# ESP32VGAv2.net
KiCad netlist of a schematic drawn in EAGLE
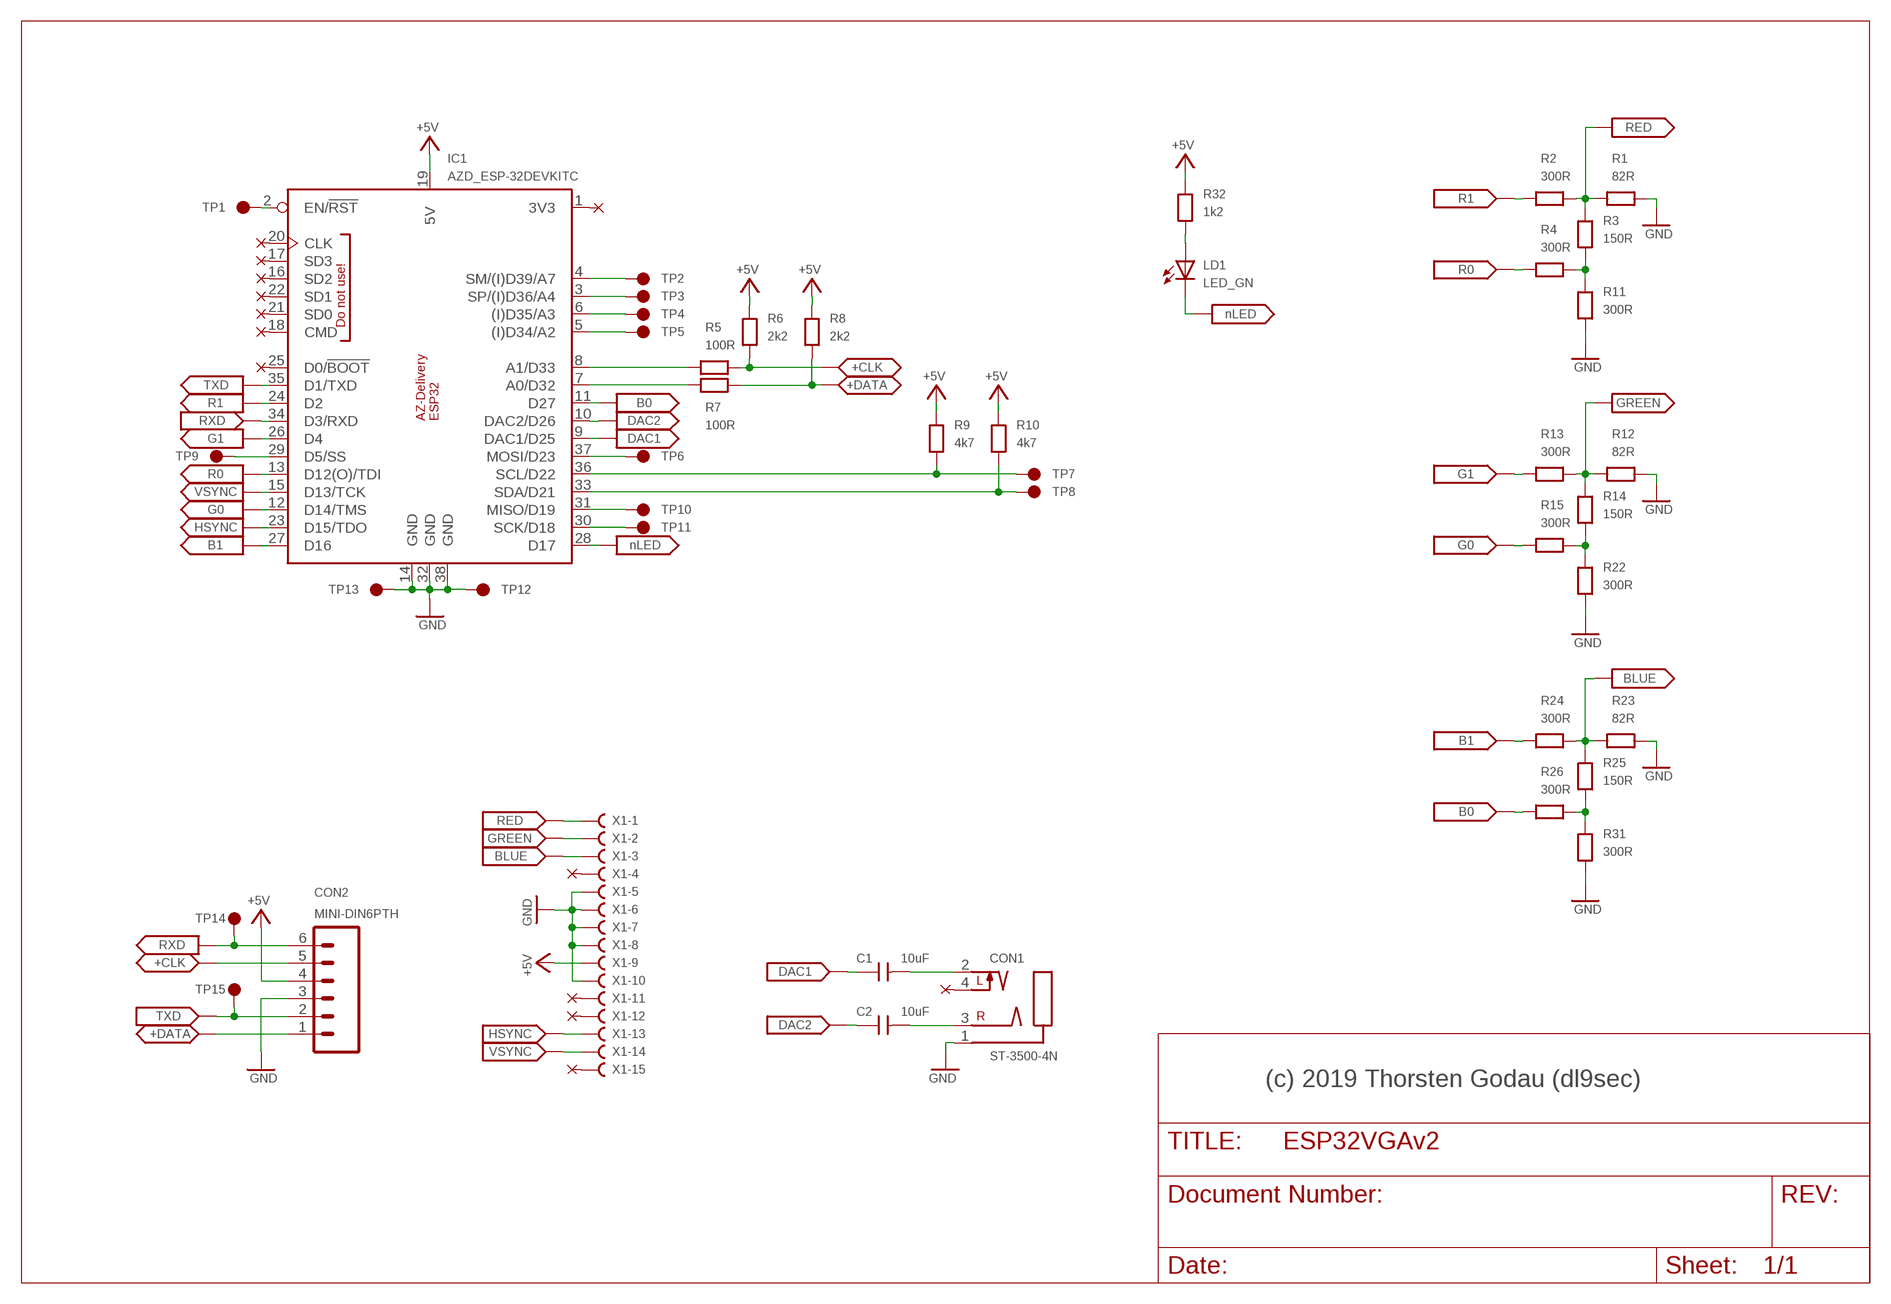
[diagram p0: schematic, sheet 1]

(export (version "E")
  (design (tool "Eeschema 10.0.6"))
  (components
    (comp (ref "C1")
      (value "10uF")
      (footprint "eagle-import:0805")
      (libsource (lib "eagle-import") (part "C0805"))
    )
    (comp (ref "C2")
      (value "10uF")
      (footprint "eagle-import:0805")
      (libsource (lib "eagle-import") (part "C0805"))
    )
    (comp (ref "CON1")
      (value "ST-3500-4N")
      (footprint "eagle-import:ST-3500-4N")
      (libsource (lib "eagle-import") (part "ST-3500-4N"))
    )
    (comp (ref "CON2")
      (value "MINI-DIN6PTH")
      (footprint "eagle-import:MINI-DIN6")
      (libsource (lib "eagle-import") (part "MINI-DIN6PTH"))
    )
    (comp (ref "IC1")
      (value "AZD_ESP-32DEVKITC")
      (footprint "eagle-import:AZD_ESP-32DEVKITC")
      (libsource (lib "eagle-import") (part "AZD_ESP-32DEVKITC"))
    )
    (comp (ref "LD1")
      (value "LED_GN")
      (footprint "eagle-import:LED3MMH")
      (libsource (lib "eagle-import") (part "LED_3MM_GN_H"))
    )
    (comp (ref "R1")
      (value "82R")
      (footprint "eagle-import:0805")
      (libsource (lib "eagle-import") (part "R0805"))
    )
    (comp (ref "R2")
      (value "300R")
      (footprint "eagle-import:0805")
      (libsource (lib "eagle-import") (part "R0805"))
    )
    (comp (ref "R3")
      (value "150R")
      (footprint "eagle-import:0805")
      (libsource (lib "eagle-import") (part "R0805"))
    )
    (comp (ref "R4")
      (value "300R")
      (footprint "eagle-import:0805")
      (libsource (lib "eagle-import") (part "R0805"))
    )
    (comp (ref "R5")
      (value "100R")
      (footprint "eagle-import:0805")
      (libsource (lib "eagle-import") (part "R0805"))
    )
    (comp (ref "R6")
      (value "2k2")
      (footprint "eagle-import:0805")
      (libsource (lib "eagle-import") (part "R0805"))
    )
    (comp (ref "R7")
      (value "100R")
      (footprint "eagle-import:0805")
      (libsource (lib "eagle-import") (part "R0805"))
    )
    (comp (ref "R8")
      (value "2k2")
      (footprint "eagle-import:0805")
      (libsource (lib "eagle-import") (part "R0805"))
    )
    (comp (ref "R9")
      (value "4k7")
      (footprint "eagle-import:0805")
      (libsource (lib "eagle-import") (part "R0805"))
    )
    (comp (ref "R10")
      (value "4k7")
      (footprint "eagle-import:0805")
      (libsource (lib "eagle-import") (part "R0805"))
    )
    (comp (ref "R11")
      (value "300R")
      (footprint "eagle-import:0805")
      (libsource (lib "eagle-import") (part "R0805"))
    )
    (comp (ref "R12")
      (value "82R")
      (footprint "eagle-import:0805")
      (libsource (lib "eagle-import") (part "R0805"))
    )
    (comp (ref "R13")
      (value "300R")
      (footprint "eagle-import:0805")
      (libsource (lib "eagle-import") (part "R0805"))
    )
    (comp (ref "R14")
      (value "150R")
      (footprint "eagle-import:0805")
      (libsource (lib "eagle-import") (part "R0805"))
    )
    (comp (ref "R15")
      (value "300R")
      (footprint "eagle-import:0805")
      (libsource (lib "eagle-import") (part "R0805"))
    )
    (comp (ref "R22")
      (value "300R")
      (footprint "eagle-import:0805")
      (libsource (lib "eagle-import") (part "R0805"))
    )
    (comp (ref "R23")
      (value "82R")
      (footprint "eagle-import:0805")
      (libsource (lib "eagle-import") (part "R0805"))
    )
    (comp (ref "R24")
      (value "300R")
      (footprint "eagle-import:0805")
      (libsource (lib "eagle-import") (part "R0805"))
    )
    (comp (ref "R25")
      (value "150R")
      (footprint "eagle-import:0805")
      (libsource (lib "eagle-import") (part "R0805"))
    )
    (comp (ref "R26")
      (value "300R")
      (footprint "eagle-import:0805")
      (libsource (lib "eagle-import") (part "R0805"))
    )
    (comp (ref "R31")
      (value "300R")
      (footprint "eagle-import:0805")
      (libsource (lib "eagle-import") (part "R0805"))
    )
    (comp (ref "R32")
      (value "1k2")
      (footprint "eagle-import:0805")
      (libsource (lib "eagle-import") (part "R0805"))
    )
    (comp (ref "TP1")
      (value "TESTPINTHT")
      (footprint "eagle-import:TESTPIN_THT")
      (libsource (lib "eagle-import") (part "TESTPINTHT"))
    )
    (comp (ref "TP2")
      (value "TESTPINTHT")
      (footprint "eagle-import:TESTPIN_THT")
      (libsource (lib "eagle-import") (part "TESTPINTHT"))
    )
    (comp (ref "TP3")
      (value "TESTPINTHT")
      (footprint "eagle-import:TESTPIN_THT")
      (libsource (lib "eagle-import") (part "TESTPINTHT"))
    )
    (comp (ref "TP4")
      (value "TESTPINTHT")
      (footprint "eagle-import:TESTPIN_THT")
      (libsource (lib "eagle-import") (part "TESTPINTHT"))
    )
    (comp (ref "TP5")
      (value "TESTPINTHT")
      (footprint "eagle-import:TESTPIN_THT")
      (libsource (lib "eagle-import") (part "TESTPINTHT"))
    )
    (comp (ref "TP6")
      (value "TESTPINTHT")
      (footprint "eagle-import:TESTPIN_THT")
      (libsource (lib "eagle-import") (part "TESTPINTHT"))
    )
    (comp (ref "TP7")
      (value "TESTPINTHT")
      (footprint "eagle-import:TESTPIN_THT")
      (libsource (lib "eagle-import") (part "TESTPINTHT"))
    )
    (comp (ref "TP8")
      (value "TESTPINTHT")
      (footprint "eagle-import:TESTPIN_THT")
      (libsource (lib "eagle-import") (part "TESTPINTHT"))
    )
    (comp (ref "TP9")
      (value "TESTPINTHT")
      (footprint "eagle-import:TESTPIN_THT")
      (libsource (lib "eagle-import") (part "TESTPINTHT"))
    )
    (comp (ref "TP10")
      (value "TESTPINTHT")
      (footprint "eagle-import:TESTPIN_THT")
      (libsource (lib "eagle-import") (part "TESTPINTHT"))
    )
    (comp (ref "TP11")
      (value "TESTPINTHT")
      (footprint "eagle-import:TESTPIN_THT")
      (libsource (lib "eagle-import") (part "TESTPINTHT"))
    )
    (comp (ref "TP12")
      (value "TESTPINTHT")
      (footprint "eagle-import:TESTPIN_THT")
      (libsource (lib "eagle-import") (part "TESTPINTHT"))
    )
    (comp (ref "TP13")
      (value "TESTPINTHT")
      (footprint "eagle-import:TESTPIN_THT")
      (libsource (lib "eagle-import") (part "TESTPINTHT"))
    )
    (comp (ref "TP14")
      (value "TESTPINTHT")
      (footprint "eagle-import:TESTPIN_THT")
      (libsource (lib "eagle-import") (part "TESTPINTHT"))
    )
    (comp (ref "TP15")
      (value "TESTPINTHT")
      (footprint "eagle-import:TESTPIN_THT")
      (libsource (lib "eagle-import") (part "TESTPINTHT"))
    )
    (comp (ref "X1")
      (value "HF15HS")
      (footprint "eagle-import:HDF15H")
      (libsource (lib "eagle-import") (part "HF15?SH"))
    )
  )
  (nets
    (net (code "1") (name "+5V") (class "Default")
      (node (ref "CON2") (pin "4") (pinfunction "4_4") (pintype "passive"))
      (node (ref "IC1") (pin "19") (pinfunction "5V_19") (pintype "power_in"))
      (node (ref "R10") (pin "2") (pinfunction "2_2") (pintype "passive"))
      (node (ref "R32") (pin "2") (pinfunction "2_2") (pintype "passive"))
      (node (ref "R6") (pin "2") (pinfunction "2_2") (pintype "passive"))
      (node (ref "R8") (pin "2") (pinfunction "2_2") (pintype "passive"))
      (node (ref "R9") (pin "2") (pinfunction "2_2") (pintype "passive"))
      (node (ref "X1") (pin "9") (pinfunction "F_9") (pintype "passive"))
    )
    (net (code "2") (name "/+CLK") (class "Default")
      (node (ref "CON2") (pin "5") (pinfunction "5_5") (pintype "passive"))
      (node (ref "R5") (pin "2") (pinfunction "2_2") (pintype "passive"))
      (node (ref "R6") (pin "1") (pinfunction "1_1") (pintype "passive"))
    )
    (net (code "3") (name "/+DATA") (class "Default")
      (node (ref "CON2") (pin "1") (pinfunction "1_1") (pintype "passive"))
      (node (ref "R7") (pin "2") (pinfunction "2_2") (pintype "passive"))
      (node (ref "R8") (pin "1") (pinfunction "1_1") (pintype "passive"))
    )
    (net (code "4") (name "/B0") (class "Default")
      (node (ref "IC1") (pin "11") (pinfunction "D27_11") (pintype "bidirectional"))
      (node (ref "R26") (pin "1") (pinfunction "1_1") (pintype "passive"))
    )
    (net (code "5") (name "/B1") (class "Default")
      (node (ref "IC1") (pin "27") (pinfunction "D16_27") (pintype "bidirectional"))
      (node (ref "R24") (pin "1") (pinfunction "1_1") (pintype "passive"))
    )
    (net (code "6") (name "/BLUE") (class "Default")
      (node (ref "R23") (pin "1") (pinfunction "1_1") (pintype "passive"))
      (node (ref "R24") (pin "2") (pinfunction "2_2") (pintype "passive"))
      (node (ref "R25") (pin "2") (pinfunction "2_2") (pintype "passive"))
      (node (ref "X1") (pin "3") (pinfunction "F_3") (pintype "passive"))
    )
    (net (code "7") (name "/DAC1") (class "Default")
      (node (ref "C1") (pin "1") (pinfunction "1_1") (pintype "passive"))
      (node (ref "IC1") (pin "9") (pinfunction "DAC1/D25_9") (pintype "bidirectional"))
    )
    (net (code "8") (name "/DAC2") (class "Default")
      (node (ref "C2") (pin "1") (pinfunction "1_1") (pintype "passive"))
      (node (ref "IC1") (pin "10") (pinfunction "DAC2/D26_10") (pintype "bidirectional"))
    )
    (net (code "9") (name "/G0") (class "Default")
      (node (ref "IC1") (pin "12") (pinfunction "D14/TMS_12") (pintype "bidirectional"))
      (node (ref "R15") (pin "1") (pinfunction "1_1") (pintype "passive"))
    )
    (net (code "10") (name "/G1") (class "Default")
      (node (ref "IC1") (pin "26") (pinfunction "D4_26") (pintype "bidirectional"))
      (node (ref "R13") (pin "1") (pinfunction "1_1") (pintype "passive"))
    )
    (net (code "11") (name "/GREEN") (class "Default")
      (node (ref "R12") (pin "1") (pinfunction "1_1") (pintype "passive"))
      (node (ref "R13") (pin "2") (pinfunction "2_2") (pintype "passive"))
      (node (ref "R14") (pin "2") (pinfunction "2_2") (pintype "passive"))
      (node (ref "X1") (pin "2") (pinfunction "F_2") (pintype "passive"))
    )
    (net (code "12") (name "/HSYNC") (class "Default")
      (node (ref "IC1") (pin "23") (pinfunction "D15/TDO_23") (pintype "bidirectional"))
      (node (ref "X1") (pin "13") (pinfunction "F_13") (pintype "passive"))
    )
    (net (code "13") (name "/NLED") (class "Default")
      (node (ref "IC1") (pin "28") (pinfunction "D17_28") (pintype "bidirectional"))
      (node (ref "LD1") (pin "K") (pinfunction "K_K") (pintype "passive"))
    )
    (net (code "14") (name "/R0") (class "Default")
      (node (ref "IC1") (pin "13") (pinfunction "D12(O)/TDI_13") (pintype "bidirectional"))
      (node (ref "R4") (pin "1") (pinfunction "1_1") (pintype "passive"))
    )
    (net (code "15") (name "/R1") (class "Default")
      (node (ref "IC1") (pin "24") (pinfunction "D2_24") (pintype "bidirectional"))
      (node (ref "R2") (pin "1") (pinfunction "1_1") (pintype "passive"))
    )
    (net (code "16") (name "/RED") (class "Default")
      (node (ref "R1") (pin "1") (pinfunction "1_1") (pintype "passive"))
      (node (ref "R2") (pin "2") (pinfunction "2_2") (pintype "passive"))
      (node (ref "R3") (pin "2") (pinfunction "2_2") (pintype "passive"))
      (node (ref "X1") (pin "1") (pinfunction "F_1") (pintype "passive"))
    )
    (net (code "17") (name "/RXD") (class "Default")
      (node (ref "CON2") (pin "6") (pinfunction "6_6") (pintype "passive"))
      (node (ref "IC1") (pin "34") (pinfunction "D3/RXD_34") (pintype "bidirectional"))
      (node (ref "TP14") (pin "1") (pinfunction "TP_1") (pintype "passive"))
    )
    (net (code "18") (name "/TXD") (class "Default")
      (node (ref "CON2") (pin "2") (pinfunction "2_2") (pintype "passive"))
      (node (ref "IC1") (pin "35") (pinfunction "D1/TXD_35") (pintype "bidirectional"))
      (node (ref "TP15") (pin "1") (pinfunction "TP_1") (pintype "passive"))
    )
    (net (code "19") (name "/VSYNC") (class "Default")
      (node (ref "IC1") (pin "15") (pinfunction "D13/TCK_15") (pintype "bidirectional"))
      (node (ref "X1") (pin "14") (pinfunction "F_14") (pintype "passive"))
    )
    (net (code "20") (name "GND") (class "Default")
      (node (ref "CON1") (pin "1") (pinfunction "COM_1") (pintype "passive"))
      (node (ref "CON2") (pin "3") (pinfunction "3_3") (pintype "passive"))
      (node (ref "IC1") (pin "14") (pinfunction "GND_14") (pintype "power_in"))
      (node (ref "IC1") (pin "32") (pinfunction "GND_32") (pintype "power_in"))
      (node (ref "IC1") (pin "38") (pinfunction "GND_38") (pintype "power_in"))
      (node (ref "R1") (pin "2") (pinfunction "2_2") (pintype "passive"))
      (node (ref "R11") (pin "1") (pinfunction "1_1") (pintype "passive"))
      (node (ref "R12") (pin "2") (pinfunction "2_2") (pintype "passive"))
      (node (ref "R22") (pin "1") (pinfunction "1_1") (pintype "passive"))
      (node (ref "R23") (pin "2") (pinfunction "2_2") (pintype "passive"))
      (node (ref "R31") (pin "1") (pinfunction "1_1") (pintype "passive"))
      (node (ref "TP12") (pin "1") (pinfunction "TP_1") (pintype "passive"))
      (node (ref "TP13") (pin "1") (pinfunction "TP_1") (pintype "passive"))
      (node (ref "X1") (pin "10") (pinfunction "F_10") (pintype "passive"))
      (node (ref "X1") (pin "5") (pinfunction "F_5") (pintype "passive"))
      (node (ref "X1") (pin "6") (pinfunction "F_6") (pintype "passive"))
      (node (ref "X1") (pin "7") (pinfunction "F_7") (pintype "passive"))
      (node (ref "X1") (pin "8") (pinfunction "F_8") (pintype "passive"))
    )
    (net (code "21") (name "Net-(CON1-L)") (class "Default")
      (node (ref "C1") (pin "2") (pinfunction "2_2") (pintype "passive"))
      (node (ref "CON1") (pin "2") (pinfunction "L_2") (pintype "passive"))
    )
    (net (code "22") (name "Net-(CON1-R)") (class "Default")
      (node (ref "C2") (pin "2") (pinfunction "2_2") (pintype "passive"))
      (node (ref "CON1") (pin "3") (pinfunction "R_3") (pintype "passive"))
    )
    (net (code "23") (name "Net-(IC1-(I)D34{slash}A2)") (class "Default")
      (node (ref "IC1") (pin "5") (pinfunction "(I)D34/A2_5") (pintype "input"))
      (node (ref "TP5") (pin "1") (pinfunction "TP_1") (pintype "passive"))
    )
    (net (code "24") (name "Net-(IC1-(I)D35{slash}A3)") (class "Default")
      (node (ref "IC1") (pin "6") (pinfunction "(I)D35/A3_6") (pintype "input"))
      (node (ref "TP4") (pin "1") (pinfunction "TP_1") (pintype "passive"))
    )
    (net (code "25") (name "Net-(IC1-A0{slash}D32)") (class "Default")
      (node (ref "IC1") (pin "7") (pinfunction "A0/D32_7") (pintype "bidirectional"))
      (node (ref "R7") (pin "1") (pinfunction "1_1") (pintype "passive"))
    )
    (net (code "26") (name "Net-(IC1-A1{slash}D33)") (class "Default")
      (node (ref "IC1") (pin "8") (pinfunction "A1/D33_8") (pintype "bidirectional"))
      (node (ref "R5") (pin "1") (pinfunction "1_1") (pintype "passive"))
    )
    (net (code "27") (name "Net-(IC1-D5{slash}SS)") (class "Default")
      (node (ref "IC1") (pin "29") (pinfunction "D5/SS_29") (pintype "bidirectional"))
      (node (ref "TP9") (pin "1") (pinfunction "TP_1") (pintype "passive"))
    )
    (net (code "28") (name "Net-(IC1-EN{slash}~{RST})") (class "Default")
      (node (ref "IC1") (pin "2") (pinfunction "EN/~{RST}_2") (pintype "input"))
      (node (ref "TP1") (pin "1") (pinfunction "TP_1") (pintype "passive"))
    )
    (net (code "29") (name "Net-(IC1-MISO{slash}D19)") (class "Default")
      (node (ref "IC1") (pin "31") (pinfunction "MISO/D19_31") (pintype "bidirectional"))
      (node (ref "TP10") (pin "1") (pinfunction "TP_1") (pintype "passive"))
    )
    (net (code "30") (name "Net-(IC1-MOSI{slash}D23)") (class "Default")
      (node (ref "IC1") (pin "37") (pinfunction "MOSI/D23_37") (pintype "bidirectional"))
      (node (ref "TP6") (pin "1") (pinfunction "TP_1") (pintype "passive"))
    )
    (net (code "31") (name "Net-(IC1-SCK{slash}D18)") (class "Default")
      (node (ref "IC1") (pin "30") (pinfunction "SCK/D18_30") (pintype "bidirectional"))
      (node (ref "TP11") (pin "1") (pinfunction "TP_1") (pintype "passive"))
    )
    (net (code "32") (name "Net-(IC1-SCL{slash}D22)") (class "Default")
      (node (ref "IC1") (pin "36") (pinfunction "SCL/D22_36") (pintype "bidirectional"))
      (node (ref "R9") (pin "1") (pinfunction "1_1") (pintype "passive"))
      (node (ref "TP7") (pin "1") (pinfunction "TP_1") (pintype "passive"))
    )
    (net (code "33") (name "Net-(IC1-SDA{slash}D21)") (class "Default")
      (node (ref "IC1") (pin "33") (pinfunction "SDA/D21_33") (pintype "bidirectional"))
      (node (ref "R10") (pin "1") (pinfunction "1_1") (pintype "passive"))
      (node (ref "TP8") (pin "1") (pinfunction "TP_1") (pintype "passive"))
    )
    (net (code "34") (name "Net-(IC1-SM{slash}(I)D39{slash}A7)") (class "Default")
      (node (ref "IC1") (pin "4") (pinfunction "SM/(I)D39/A7_4") (pintype "input"))
      (node (ref "TP2") (pin "1") (pinfunction "TP_1") (pintype "passive"))
    )
    (net (code "35") (name "Net-(IC1-SP{slash}(I)D36{slash}A4)") (class "Default")
      (node (ref "IC1") (pin "3") (pinfunction "SP/(I)D36/A4_3") (pintype "input"))
      (node (ref "TP3") (pin "1") (pinfunction "TP_1") (pintype "passive"))
    )
    (net (code "36") (name "Net-(LD1-PadA)") (class "Default")
      (node (ref "LD1") (pin "A") (pinfunction "A_A") (pintype "passive"))
      (node (ref "R32") (pin "1") (pinfunction "1_1") (pintype "passive"))
    )
    (net (code "37") (name "Net-(R11-Pad2)") (class "Default")
      (node (ref "R11") (pin "2") (pinfunction "2_2") (pintype "passive"))
      (node (ref "R3") (pin "1") (pinfunction "1_1") (pintype "passive"))
      (node (ref "R4") (pin "2") (pinfunction "2_2") (pintype "passive"))
    )
    (net (code "38") (name "Net-(R14-Pad1)") (class "Default")
      (node (ref "R14") (pin "1") (pinfunction "1_1") (pintype "passive"))
      (node (ref "R15") (pin "2") (pinfunction "2_2") (pintype "passive"))
      (node (ref "R22") (pin "2") (pinfunction "2_2") (pintype "passive"))
    )
    (net (code "39") (name "Net-(R25-Pad1)") (class "Default")
      (node (ref "R25") (pin "1") (pinfunction "1_1") (pintype "passive"))
      (node (ref "R26") (pin "2") (pinfunction "2_2") (pintype "passive"))
      (node (ref "R31") (pin "2") (pinfunction "2_2") (pintype "passive"))
    )
    (net (code "40") (name "unconnected-(CON1-LSW-Pad4)") (class "Default")
      (node (ref "CON1") (pin "4") (pinfunction "LSW_4") (pintype "passive"))
    )
    (net (code "41") (name "unconnected-(IC1-3V3-Pad1)") (class "Default")
      (node (ref "IC1") (pin "1") (pinfunction "3V3_1") (pintype "passive"))
    )
    (net (code "42") (name "unconnected-(IC1-CLK-Pad20)") (class "Default")
      (node (ref "IC1") (pin "20") (pinfunction "CLK_20") (pintype "bidirectional"))
    )
    (net (code "43") (name "unconnected-(IC1-CMD-Pad18)") (class "Default")
      (node (ref "IC1") (pin "18") (pinfunction "CMD_18") (pintype "bidirectional"))
    )
    (net (code "44") (name "unconnected-(IC1-D0{slash}~{BOOT}-Pad25)") (class "Default")
      (node (ref "IC1") (pin "25") (pinfunction "D0/~{BOOT}_25") (pintype "bidirectional"))
    )
    (net (code "45") (name "unconnected-(IC1-SD0-Pad21)") (class "Default")
      (node (ref "IC1") (pin "21") (pinfunction "SD0_21") (pintype "bidirectional"))
    )
    (net (code "46") (name "unconnected-(IC1-SD1-Pad22)") (class "Default")
      (node (ref "IC1") (pin "22") (pinfunction "SD1_22") (pintype "bidirectional"))
    )
    (net (code "47") (name "unconnected-(IC1-SD2-Pad16)") (class "Default")
      (node (ref "IC1") (pin "16") (pinfunction "SD2_16") (pintype "bidirectional"))
    )
    (net (code "48") (name "unconnected-(IC1-SD3-Pad17)") (class "Default")
      (node (ref "IC1") (pin "17") (pinfunction "SD3_17") (pintype "bidirectional"))
    )
    (net (code "49") (name "unconnected-(X1C-F-Pad11)") (class "Default")
      (node (ref "X1") (pin "11") (pinfunction "F_11") (pintype "passive"))
    )
    (net (code "50") (name "unconnected-(X1D-F-Pad12)") (class "Default")
      (node (ref "X1") (pin "12") (pinfunction "F_12") (pintype "passive"))
    )
    (net (code "51") (name "unconnected-(X1G-F-Pad15)") (class "Default")
      (node (ref "X1") (pin "15") (pinfunction "F_15") (pintype "passive"))
    )
    (net (code "52") (name "unconnected-(X1J-F-Pad4)") (class "Default")
      (node (ref "X1") (pin "4") (pinfunction "F_4") (pintype "passive"))
    )
  )
)
